# pca9535bo.net
KiCad netlist of a schematic drawn in EAGLE
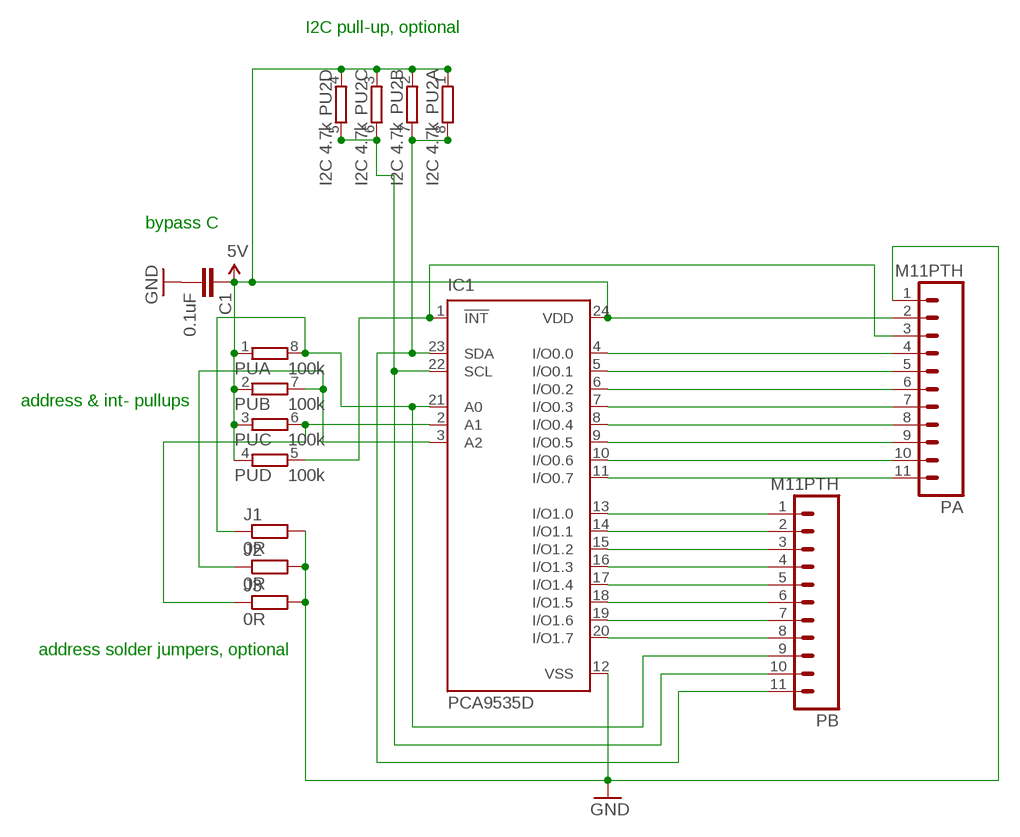
[diagram p0: schematic, sheet 1]

(export (version "E")
  (design (tool "Eeschema 10.0.6"))
  (components
    (comp (ref "C1")
      (value "0.1uF")
      (footprint "eagle-import:C0805K")
      (libsource (lib "eagle-import") (part "C-EUC0805K"))
    )
    (comp (ref "IC1")
      (value "PCA9535D")
      (footprint "eagle-import:SO24")
      (fields (field (name "MPN") "PCA9555DW"))
      (libsource (lib "eagle-import") (part "PCA9555D"))
    )
    (comp (ref "J1")
      (value "0R")
      (footprint "eagle-import:R0603")
      (libsource (lib "eagle-import") (part "R-EU_R0603"))
    )
    (comp (ref "J2")
      (value "0R")
      (footprint "eagle-import:R0603")
      (libsource (lib "eagle-import") (part "R-EU_R0603"))
    )
    (comp (ref "J3")
      (value "0R")
      (footprint "eagle-import:R0603")
      (libsource (lib "eagle-import") (part "R-EU_R0603"))
    )
    (comp (ref "PA")
      (value "M11PTH")
      (footprint "eagle-import:1X11")
      (libsource (lib "eagle-import") (part "M11PTH"))
    )
    (comp (ref "PB")
      (value "M11PTH")
      (footprint "eagle-import:1X11")
      (libsource (lib "eagle-import") (part "M11PTH"))
    )
    (comp (ref "PU")
      (value "100k")
      (footprint "eagle-import:CAY16")
      (libsource (lib "eagle-import") (part "4R-NCAY16"))
    )
    (comp (ref "PU2")
      (value "I2C 4.7k")
      (footprint "eagle-import:CAY16")
      (libsource (lib "eagle-import") (part "4R-NCAY16"))
    )
  )
  (nets
    (net (code "1") (name "5V") (class "Default")
      (node (ref "C1") (pin "1") (pinfunction "1_1") (pintype "passive"))
      (node (ref "IC1") (pin "24") (pinfunction "VDD_24") (pintype "power_in"))
      (node (ref "PA") (pin "2") (pinfunction "2_2") (pintype "passive"))
      (node (ref "PU") (pin "1") (pinfunction "1_1") (pintype "passive"))
      (node (ref "PU") (pin "2") (pinfunction "1_2") (pintype "passive"))
      (node (ref "PU") (pin "3") (pinfunction "1_3") (pintype "passive"))
      (node (ref "PU") (pin "4") (pinfunction "1_4") (pintype "passive"))
      (node (ref "PU2") (pin "1") (pinfunction "1_1") (pintype "passive"))
      (node (ref "PU2") (pin "2") (pinfunction "1_2") (pintype "passive"))
      (node (ref "PU2") (pin "3") (pinfunction "1_3") (pintype "passive"))
      (node (ref "PU2") (pin "4") (pinfunction "1_4") (pintype "passive"))
    )
    (net (code "2") (name "GND") (class "Default")
      (node (ref "C1") (pin "2") (pinfunction "2_2") (pintype "passive"))
      (node (ref "IC1") (pin "12") (pinfunction "VSS_12") (pintype "power_in"))
      (node (ref "J1") (pin "2") (pinfunction "2_2") (pintype "passive"))
      (node (ref "J2") (pin "2") (pinfunction "2_2") (pintype "passive"))
      (node (ref "J3") (pin "2") (pinfunction "2_2") (pintype "passive"))
      (node (ref "PA") (pin "1") (pinfunction "1_1") (pintype "passive"))
    )
    (net (code "3") (name "Net-(IC1-A0)") (class "Default")
      (node (ref "IC1") (pin "21") (pinfunction "A0_21") (pintype "input"))
      (node (ref "J1") (pin "1") (pinfunction "1_1") (pintype "passive"))
      (node (ref "PB") (pin "9") (pinfunction "9_9") (pintype "passive"))
      (node (ref "PU") (pin "8") (pinfunction "2_8") (pintype "passive"))
    )
    (net (code "4") (name "Net-(IC1-A1)") (class "Default")
      (node (ref "IC1") (pin "2") (pinfunction "A1_2") (pintype "input"))
      (node (ref "J3") (pin "1") (pinfunction "1_1") (pintype "passive"))
      (node (ref "PU") (pin "6") (pinfunction "2_6") (pintype "passive"))
    )
    (net (code "5") (name "Net-(IC1-A2)") (class "Default")
      (node (ref "IC1") (pin "3") (pinfunction "A2_3") (pintype "input"))
      (node (ref "J2") (pin "1") (pinfunction "1_1") (pintype "passive"))
      (node (ref "PU") (pin "7") (pinfunction "2_7") (pintype "passive"))
    )
    (net (code "6") (name "Net-(IC1-I{slash}O0.0)") (class "Default")
      (node (ref "IC1") (pin "4") (pinfunction "I/O0.0_4") (pintype "bidirectional"))
      (node (ref "PA") (pin "4") (pinfunction "4_4") (pintype "passive"))
    )
    (net (code "7") (name "Net-(IC1-I{slash}O0.1)") (class "Default")
      (node (ref "IC1") (pin "5") (pinfunction "I/O0.1_5") (pintype "bidirectional"))
      (node (ref "PA") (pin "5") (pinfunction "5_5") (pintype "passive"))
    )
    (net (code "8") (name "Net-(IC1-I{slash}O0.2)") (class "Default")
      (node (ref "IC1") (pin "6") (pinfunction "I/O0.2_6") (pintype "bidirectional"))
      (node (ref "PA") (pin "6") (pinfunction "6_6") (pintype "passive"))
    )
    (net (code "9") (name "Net-(IC1-I{slash}O0.3)") (class "Default")
      (node (ref "IC1") (pin "7") (pinfunction "I/O0.3_7") (pintype "bidirectional"))
      (node (ref "PA") (pin "7") (pinfunction "7_7") (pintype "passive"))
    )
    (net (code "10") (name "Net-(IC1-I{slash}O0.4)") (class "Default")
      (node (ref "IC1") (pin "8") (pinfunction "I/O0.4_8") (pintype "bidirectional"))
      (node (ref "PA") (pin "8") (pinfunction "8_8") (pintype "passive"))
    )
    (net (code "11") (name "Net-(IC1-I{slash}O0.5)") (class "Default")
      (node (ref "IC1") (pin "9") (pinfunction "I/O0.5_9") (pintype "bidirectional"))
      (node (ref "PA") (pin "9") (pinfunction "9_9") (pintype "passive"))
    )
    (net (code "12") (name "Net-(IC1-I{slash}O0.6)") (class "Default")
      (node (ref "IC1") (pin "10") (pinfunction "I/O0.6_10") (pintype "bidirectional"))
      (node (ref "PA") (pin "10") (pinfunction "10_10") (pintype "passive"))
    )
    (net (code "13") (name "Net-(IC1-I{slash}O0.7)") (class "Default")
      (node (ref "IC1") (pin "11") (pinfunction "I/O0.7_11") (pintype "bidirectional"))
      (node (ref "PA") (pin "11") (pinfunction "11_11") (pintype "passive"))
    )
    (net (code "14") (name "Net-(IC1-I{slash}O1.0)") (class "Default")
      (node (ref "IC1") (pin "13") (pinfunction "I/O1.0_13") (pintype "bidirectional"))
      (node (ref "PB") (pin "1") (pinfunction "1_1") (pintype "passive"))
    )
    (net (code "15") (name "Net-(IC1-I{slash}O1.1)") (class "Default")
      (node (ref "IC1") (pin "14") (pinfunction "I/O1.1_14") (pintype "bidirectional"))
      (node (ref "PB") (pin "2") (pinfunction "2_2") (pintype "passive"))
    )
    (net (code "16") (name "Net-(IC1-I{slash}O1.2)") (class "Default")
      (node (ref "IC1") (pin "15") (pinfunction "I/O1.2_15") (pintype "bidirectional"))
      (node (ref "PB") (pin "3") (pinfunction "3_3") (pintype "passive"))
    )
    (net (code "17") (name "Net-(IC1-I{slash}O1.3)") (class "Default")
      (node (ref "IC1") (pin "16") (pinfunction "I/O1.3_16") (pintype "bidirectional"))
      (node (ref "PB") (pin "4") (pinfunction "4_4") (pintype "passive"))
    )
    (net (code "18") (name "Net-(IC1-I{slash}O1.4)") (class "Default")
      (node (ref "IC1") (pin "17") (pinfunction "I/O1.4_17") (pintype "bidirectional"))
      (node (ref "PB") (pin "5") (pinfunction "5_5") (pintype "passive"))
    )
    (net (code "19") (name "Net-(IC1-I{slash}O1.5)") (class "Default")
      (node (ref "IC1") (pin "18") (pinfunction "I/O1.5_18") (pintype "bidirectional"))
      (node (ref "PB") (pin "6") (pinfunction "6_6") (pintype "passive"))
    )
    (net (code "20") (name "Net-(IC1-I{slash}O1.6)") (class "Default")
      (node (ref "IC1") (pin "19") (pinfunction "I/O1.6_19") (pintype "bidirectional"))
      (node (ref "PB") (pin "7") (pinfunction "7_7") (pintype "passive"))
    )
    (net (code "21") (name "Net-(IC1-I{slash}O1.7)") (class "Default")
      (node (ref "IC1") (pin "20") (pinfunction "I/O1.7_20") (pintype "bidirectional"))
      (node (ref "PB") (pin "8") (pinfunction "8_8") (pintype "passive"))
    )
    (net (code "22") (name "Net-(IC1-SCL)") (class "Default")
      (node (ref "IC1") (pin "22") (pinfunction "SCL_22") (pintype "input"))
      (node (ref "PB") (pin "10") (pinfunction "10_10") (pintype "passive"))
      (node (ref "PU2") (pin "5") (pinfunction "2_5") (pintype "passive"))
      (node (ref "PU2") (pin "6") (pinfunction "2_6") (pintype "passive"))
    )
    (net (code "23") (name "Net-(IC1-SDA)") (class "Default")
      (node (ref "IC1") (pin "23") (pinfunction "SDA_23") (pintype "bidirectional"))
      (node (ref "PB") (pin "11") (pinfunction "11_11") (pintype "passive"))
      (node (ref "PU2") (pin "7") (pinfunction "2_7") (pintype "passive"))
      (node (ref "PU2") (pin "8") (pinfunction "2_8") (pintype "passive"))
    )
    (net (code "24") (name "Net-(IC1-~{INT})") (class "Default")
      (node (ref "IC1") (pin "1") (pinfunction "~{INT}_1") (pintype "output"))
      (node (ref "PA") (pin "3") (pinfunction "3_3") (pintype "passive"))
      (node (ref "PU") (pin "5") (pinfunction "2_5") (pintype "passive"))
    )
  )
)
